# AFE.net
KiCad netlist of a schematic drawn in Altium Designer
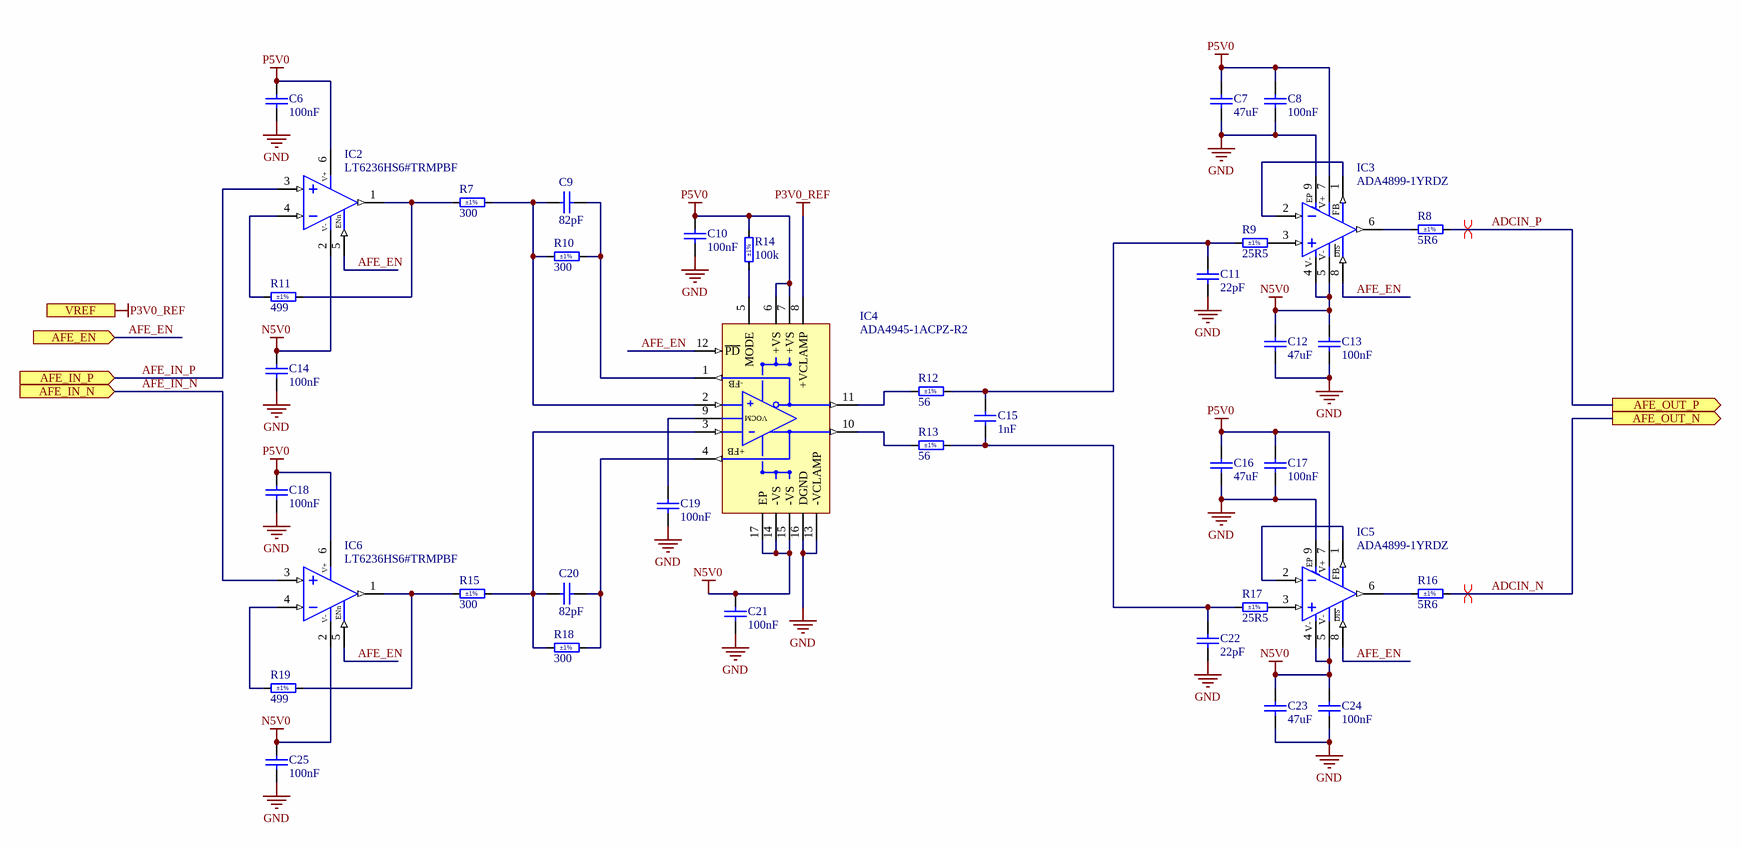
[diagram p0: AFE.SchDoc]

(export (version "E")
  (design (tool "Eeschema 10.0.6"))
  (components
    (comp (ref "C6")
      (value "100nF")
      (footprint "CAPC1005X55N")
      (description "Non-polarised capacitor")
      (fields
        (field (name "PART NUMBER") "CC0402_100NF_50V_10%_X7R")
        (field (name "VOLTAGE") "50V")
        (field (name "AUTHOR") "CERN DEM MR")
      )
      (libsource (lib "Capacitors") (part "Capacitor - non polarized"))
    )
    (comp (ref "C7")
      (value "47uF")
      (footprint "CAPC3216X180N")
      (description "Non-polarised capacitor")
      (fields
        (field (name "PART NUMBER") "CC1206_47UF_25V_20%_X5R")
        (field (name "VOLTAGE") "25V")
        (field (name "AUTHOR") "CERN DEM JLC")
      )
      (libsource (lib "Capacitors") (part "Capacitor - non polarized"))
    )
    (comp (ref "C8")
      (value "100nF")
      (footprint "CAPC1005X55N")
      (description "Non-polarised capacitor")
      (fields
        (field (name "PART NUMBER") "CC0402_100NF_50V_10%_X7R")
        (field (name "VOLTAGE") "50V")
        (field (name "AUTHOR") "CERN DEM MR")
      )
      (libsource (lib "Capacitors") (part "Capacitor - non polarized"))
    )
    (comp (ref "C9")
      (value "82pF")
      (footprint "CAPC1005X55N")
      (description "Non-polarised capacitor")
      (fields
        (field (name "PART NUMBER") "CC0402_82PF_25V_1%_C0G_KEMET_HiQ-CBR")
        (field (name "VOLTAGE") "25V")
        (field (name "AUTHOR") "CERN DEM MR")
      )
      (libsource (lib "Capacitors") (part "Capacitor - non polarized"))
    )
    (comp (ref "C10")
      (value "100nF")
      (footprint "CAPC1005X55N")
      (description "Non-polarised capacitor")
      (fields
        (field (name "PART NUMBER") "CC0402_100NF_50V_10%_X7R")
        (field (name "VOLTAGE") "50V")
        (field (name "AUTHOR") "CERN DEM MR")
      )
      (libsource (lib "Capacitors") (part "Capacitor - non polarized"))
    )
    (comp (ref "C11")
      (value "22pF")
      (footprint "CAPC1005X55N")
      (description "Non-polarised capacitor")
      (fields
        (field (name "PART NUMBER") "CC0402_22PF_50V_5%_C0G")
        (field (name "VOLTAGE") "50V")
        (field (name "AUTHOR") "CERN DEM JLC")
      )
      (libsource (lib "Capacitors") (part "Capacitor - non polarized"))
    )
    (comp (ref "C12")
      (value "47uF")
      (footprint "CAPC3216X180N")
      (description "Non-polarised capacitor")
      (fields
        (field (name "PART NUMBER") "CC1206_47UF_25V_20%_X5R")
        (field (name "VOLTAGE") "25V")
        (field (name "AUTHOR") "CERN DEM JLC")
      )
      (libsource (lib "Capacitors") (part "Capacitor - non polarized"))
    )
    (comp (ref "C13")
      (value "100nF")
      (footprint "CAPC1005X55N")
      (description "Non-polarised capacitor")
      (fields
        (field (name "PART NUMBER") "CC0402_100NF_50V_10%_X7R")
        (field (name "VOLTAGE") "50V")
        (field (name "AUTHOR") "CERN DEM MR")
      )
      (libsource (lib "Capacitors") (part "Capacitor - non polarized"))
    )
    (comp (ref "C14")
      (value "100nF")
      (footprint "CAPC1005X55N")
      (description "Non-polarised capacitor")
      (fields
        (field (name "PART NUMBER") "CC0402_100NF_50V_10%_X7R")
        (field (name "VOLTAGE") "50V")
        (field (name "AUTHOR") "CERN DEM MR")
      )
      (libsource (lib "Capacitors") (part "Capacitor - non polarized"))
    )
    (comp (ref "C15")
      (value "1nF")
      (footprint "CAPC1005X55N")
      (description "Non-polarised capacitor")
      (fields
        (field (name "PART NUMBER") "CC0402_1NF_50V_10%_X7R")
        (field (name "VOLTAGE") "50V")
        (field (name "AUTHOR") "CERN DEM JLC")
      )
      (libsource (lib "Capacitors") (part "Capacitor - non polarized"))
    )
    (comp (ref "C16")
      (value "47uF")
      (footprint "CAPC3216X180N")
      (description "Non-polarised capacitor")
      (fields
        (field (name "PART NUMBER") "CC1206_47UF_25V_20%_X5R")
        (field (name "VOLTAGE") "25V")
        (field (name "AUTHOR") "CERN DEM JLC")
      )
      (libsource (lib "Capacitors") (part "Capacitor - non polarized"))
    )
    (comp (ref "C17")
      (value "100nF")
      (footprint "CAPC1005X55N")
      (description "Non-polarised capacitor")
      (fields
        (field (name "PART NUMBER") "CC0402_100NF_50V_10%_X7R")
        (field (name "VOLTAGE") "50V")
        (field (name "AUTHOR") "CERN DEM MR")
      )
      (libsource (lib "Capacitors") (part "Capacitor - non polarized"))
    )
    (comp (ref "C18")
      (value "100nF")
      (footprint "CAPC1005X55N")
      (description "Non-polarised capacitor")
      (fields
        (field (name "PART NUMBER") "CC0402_100NF_50V_10%_X7R")
        (field (name "VOLTAGE") "50V")
        (field (name "AUTHOR") "CERN DEM MR")
      )
      (libsource (lib "Capacitors") (part "Capacitor - non polarized"))
    )
    (comp (ref "C19")
      (value "100nF")
      (footprint "CAPC1005X55N")
      (description "Non-polarised capacitor")
      (fields
        (field (name "PART NUMBER") "CC0402_100NF_50V_10%_X7R")
        (field (name "VOLTAGE") "50V")
        (field (name "AUTHOR") "CERN DEM MR")
      )
      (libsource (lib "Capacitors") (part "Capacitor - non polarized"))
    )
    (comp (ref "C20")
      (value "82pF")
      (footprint "CAPC1005X55N")
      (description "Non-polarised capacitor")
      (fields
        (field (name "PART NUMBER") "CC0402_82PF_25V_1%_C0G_KEMET_HiQ-CBR")
        (field (name "VOLTAGE") "25V")
        (field (name "AUTHOR") "CERN DEM MR")
      )
      (libsource (lib "Capacitors") (part "Capacitor - non polarized"))
    )
    (comp (ref "C21")
      (value "100nF")
      (footprint "CAPC1005X55N")
      (description "Non-polarised capacitor")
      (fields
        (field (name "PART NUMBER") "CC0402_100NF_50V_10%_X7R")
        (field (name "VOLTAGE") "50V")
        (field (name "AUTHOR") "CERN DEM MR")
      )
      (libsource (lib "Capacitors") (part "Capacitor - non polarized"))
    )
    (comp (ref "C22")
      (value "22pF")
      (footprint "CAPC1005X55N")
      (description "Non-polarised capacitor")
      (fields
        (field (name "PART NUMBER") "CC0402_22PF_50V_5%_C0G")
        (field (name "VOLTAGE") "50V")
        (field (name "AUTHOR") "CERN DEM JLC")
      )
      (libsource (lib "Capacitors") (part "Capacitor - non polarized"))
    )
    (comp (ref "C23")
      (value "47uF")
      (footprint "CAPC3216X180N")
      (description "Non-polarised capacitor")
      (fields
        (field (name "PART NUMBER") "CC1206_47UF_25V_20%_X5R")
        (field (name "VOLTAGE") "25V")
        (field (name "AUTHOR") "CERN DEM JLC")
      )
      (libsource (lib "Capacitors") (part "Capacitor - non polarized"))
    )
    (comp (ref "C24")
      (value "100nF")
      (footprint "CAPC1005X55N")
      (description "Non-polarised capacitor")
      (fields
        (field (name "PART NUMBER") "CC0402_100NF_50V_10%_X7R")
        (field (name "VOLTAGE") "50V")
        (field (name "AUTHOR") "CERN DEM MR")
      )
      (libsource (lib "Capacitors") (part "Capacitor - non polarized"))
    )
    (comp (ref "C25")
      (value "100nF")
      (footprint "CAPC1005X55N")
      (description "Non-polarised capacitor")
      (fields
        (field (name "PART NUMBER") "CC0402_100NF_50V_10%_X7R")
        (field (name "VOLTAGE") "50V")
        (field (name "AUTHOR") "CERN DEM MR")
      )
      (libsource (lib "Capacitors") (part "Capacitor - non polarized"))
    )
    (comp (ref "IC2")
      (value "LT6236HS6#TRMPBF")
      (footprint "SOT95P280X100-6N")
      (description "Rail-to-Rail Output 215MHz, 1.1nV/√Hz Op Amp/SAR ADC Driver")
      (fields (field (name "MANUFACTURER") "Linear Technology") (field (name "AUTHOR") "Michal Beldyga"))
      (libsource (lib "Semiconductors") (part "LT6236"))
    )
    (comp (ref "IC3")
      (value "ADA4899-1YRDZ")
      (footprint "SOIC127P600X175-9N-S229")
      (fields
        (field (name "MANUFACTURER") "ANALOG DEVICES")
        (field (name "MANUFACTURER PART NUMBER") "ADA4899-1YRD")
        (field (name "AUTHOR") "CERN DEM JLC")
      )
      (libsource (lib "ICs And Semiconductors") (part "ADA4899-1YRDZ"))
    )
    (comp (ref "IC4")
      (value "ADA4945-1ACPZ-R2")
      (footprint "QFN50P300X300X80_HS-17N")
      (description "High Speed, ±0.1 µV/˚C Offset Drift, Fully Differential ADC Driver")
      (fields (field (name "MANUFACTURER") "Analog Devices") (field (name "AUTHOR") "Michal Beldyga"))
      (libsource (lib "Semiconductors") (part "ADA4945-1"))
    )
    (comp (ref "IC5")
      (value "ADA4899-1YRDZ")
      (footprint "SOIC127P600X175-9N-S229")
      (fields
        (field (name "MANUFACTURER") "ANALOG DEVICES")
        (field (name "MANUFACTURER PART NUMBER") "ADA4899-1YRD")
        (field (name "AUTHOR") "CERN DEM JLC")
      )
      (libsource (lib "ICs And Semiconductors") (part "ADA4899-1YRDZ"))
    )
    (comp (ref "IC6")
      (value "LT6236HS6#TRMPBF")
      (footprint "SOT95P280X100-6N")
      (description "Rail-to-Rail Output 215MHz, 1.1nV/√Hz Op Amp/SAR ADC Driver")
      (fields (field (name "MANUFACTURER") "Linear Technology") (field (name "AUTHOR") "Michal Beldyga"))
      (libsource (lib "Semiconductors") (part "LT6236"))
    )
    (comp (ref "R7")
      (value "300")
      (footprint "RESC1005X40N")
      (description "Resistor - 1%")
      (fields
        (field (name "TOLERANCE") "±1%")
        (field (name "PART NUMBER") "R0402_300R_1%_0.0625W_100PPM")
        (field (name "POWER") "0.0625W")
        (field (name "AUTHOR") "CERN DEM JLC")
      )
      (libsource (lib "Resistors") (part "Resistor - 1%"))
    )
    (comp (ref "R8")
      (value "5R6")
      (footprint "RESC1608X55N")
      (description "Resistor - 1%")
      (fields
        (field (name "TOLERANCE") "±1%")
        (field (name "PART NUMBER") "R0603_5R6_1%_0.1W_200PPM")
        (field (name "POWER") "0.1W")
        (field (name "AUTHOR") "CERN DEM JLC")
      )
      (libsource (lib "Resistors") (part "Resistor - 1%"))
    )
    (comp (ref "R9")
      (value "25R5")
      (footprint "RESC1005X40N")
      (description "Resistor - 1%")
      (fields
        (field (name "TOLERANCE") "±1%")
        (field (name "PART NUMBER") "R0402_25R5_1%_0.0625W_100PPM")
        (field (name "POWER") "0.0625W")
        (field (name "AUTHOR") "CERN DEM JLC")
      )
      (libsource (lib "Resistors") (part "Resistor - 1%"))
    )
    (comp (ref "R10")
      (value "300")
      (footprint "RESC1005X40N")
      (description "Resistor - 1%")
      (fields
        (field (name "TOLERANCE") "±1%")
        (field (name "PART NUMBER") "R0402_300R_1%_0.0625W_100PPM")
        (field (name "POWER") "0.0625W")
        (field (name "AUTHOR") "CERN DEM JLC")
      )
      (libsource (lib "Resistors") (part "Resistor - 1%"))
    )
    (comp (ref "R11")
      (value "499")
      (footprint "RESC1005X40N")
      (description "Resistor - 1%")
      (fields
        (field (name "TOLERANCE") "±1%")
        (field (name "PART NUMBER") "R0402_499R_1%_0.1W_100PPM")
        (field (name "POWER") "0.1W")
        (field (name "AUTHOR") "CERN DEM MR")
      )
      (libsource (lib "Resistors") (part "Resistor - 1%"))
    )
    (comp (ref "R12")
      (value "56")
      (footprint "RESC1005X40N")
      (description "Resistor - 1%")
      (fields
        (field (name "TOLERANCE") "±1%")
        (field (name "PART NUMBER") "R0402_56R_1%_0.0625W_100PPM")
        (field (name "POWER") "0.0625W")
        (field (name "AUTHOR") "CERN DEM JLC")
      )
      (libsource (lib "Resistors") (part "Resistor - 1%"))
    )
    (comp (ref "R13")
      (value "56")
      (footprint "RESC1005X40N")
      (description "Resistor - 1%")
      (fields
        (field (name "TOLERANCE") "±1%")
        (field (name "PART NUMBER") "R0402_56R_1%_0.0625W_100PPM")
        (field (name "POWER") "0.0625W")
        (field (name "AUTHOR") "CERN DEM JLC")
      )
      (libsource (lib "Resistors") (part "Resistor - 1%"))
    )
    (comp (ref "R14")
      (value "100k")
      (footprint "RESC1005X40N")
      (description "Resistor - 1%")
      (fields
        (field (name "TOLERANCE") "±1%")
        (field (name "PART NUMBER") "R0402_100K_1%_0.0625W_100PPM")
        (field (name "POWER") "0.0625W")
        (field (name "AUTHOR") "CERN DEM JLC")
      )
      (libsource (lib "Resistors") (part "Resistor - 1%"))
    )
    (comp (ref "R15")
      (value "300")
      (footprint "RESC1005X40N")
      (description "Resistor - 1%")
      (fields
        (field (name "TOLERANCE") "±1%")
        (field (name "PART NUMBER") "R0402_300R_1%_0.0625W_100PPM")
        (field (name "POWER") "0.0625W")
        (field (name "AUTHOR") "CERN DEM JLC")
      )
      (libsource (lib "Resistors") (part "Resistor - 1%"))
    )
    (comp (ref "R16")
      (value "5R6")
      (footprint "RESC1608X55N")
      (description "Resistor - 1%")
      (fields
        (field (name "TOLERANCE") "±1%")
        (field (name "PART NUMBER") "R0603_5R6_1%_0.1W_200PPM")
        (field (name "POWER") "0.1W")
        (field (name "AUTHOR") "CERN DEM JLC")
      )
      (libsource (lib "Resistors") (part "Resistor - 1%"))
    )
    (comp (ref "R17")
      (value "25R5")
      (footprint "RESC1005X40N")
      (description "Resistor - 1%")
      (fields
        (field (name "TOLERANCE") "±1%")
        (field (name "PART NUMBER") "R0402_25R5_1%_0.0625W_100PPM")
        (field (name "POWER") "0.0625W")
        (field (name "AUTHOR") "CERN DEM JLC")
      )
      (libsource (lib "Resistors") (part "Resistor - 1%"))
    )
    (comp (ref "R18")
      (value "300")
      (footprint "RESC1005X40N")
      (description "Resistor - 1%")
      (fields
        (field (name "TOLERANCE") "±1%")
        (field (name "PART NUMBER") "R0402_300R_1%_0.0625W_100PPM")
        (field (name "POWER") "0.0625W")
        (field (name "AUTHOR") "CERN DEM JLC")
      )
      (libsource (lib "Resistors") (part "Resistor - 1%"))
    )
    (comp (ref "R19")
      (value "499")
      (footprint "RESC1005X40N")
      (description "Resistor - 1%")
      (fields
        (field (name "TOLERANCE") "±1%")
        (field (name "PART NUMBER") "R0402_499R_1%_0.1W_100PPM")
        (field (name "POWER") "0.1W")
        (field (name "AUTHOR") "CERN DEM MR")
      )
      (libsource (lib "Resistors") (part "Resistor - 1%"))
    )
  )
  (nets
    (net (code "1") (name "/ADCIN_N") (class "Default")
      (node (ref "R16") (pin "2") (pinfunction "2_2") (pintype "passive"))
    )
    (net (code "2") (name "/ADCIN_P") (class "Default")
      (node (ref "R8") (pin "2") (pinfunction "2_2") (pintype "passive"))
    )
    (net (code "3") (name "/AFE_EN") (class "Default")
      (node (ref "IC2") (pin "5") (pinfunction "~{DIS}_5") (pintype "input"))
      (node (ref "IC3") (pin "8") (pinfunction "~{DIS}_8") (pintype "input"))
      (node (ref "IC4") (pin "12") (pinfunction "~{PD}_12") (pintype "input"))
      (node (ref "IC5") (pin "8") (pinfunction "~{DIS}_8") (pintype "input"))
      (node (ref "IC6") (pin "5") (pinfunction "~{DIS}_5") (pintype "input"))
    )
    (net (code "4") (name "/AFE_IN_N") (class "Default")
      (node (ref "IC6") (pin "3") (pinfunction "VP_3") (pintype "input"))
    )
    (net (code "5") (name "/AFE_IN_P") (class "Default")
      (node (ref "IC2") (pin "3") (pinfunction "VP_3") (pintype "input"))
    )
    (net (code "6") (name "GND") (class "Default")
      (node (ref "C10") (pin "1") (pinfunction "1_1") (pintype "passive"))
      (node (ref "C11") (pin "1") (pinfunction "1_1") (pintype "passive"))
      (node (ref "C12") (pin "1") (pinfunction "1_1") (pintype "passive"))
      (node (ref "C13") (pin "1") (pinfunction "1_1") (pintype "passive"))
      (node (ref "C14") (pin "1") (pinfunction "1_1") (pintype "passive"))
      (node (ref "C16") (pin "1") (pinfunction "1_1") (pintype "passive"))
      (node (ref "C17") (pin "1") (pinfunction "1_1") (pintype "passive"))
      (node (ref "C18") (pin "1") (pinfunction "1_1") (pintype "passive"))
      (node (ref "C19") (pin "1") (pinfunction "1_1") (pintype "passive"))
      (node (ref "C21") (pin "1") (pinfunction "1_1") (pintype "passive"))
      (node (ref "C22") (pin "1") (pinfunction "1_1") (pintype "passive"))
      (node (ref "C23") (pin "1") (pinfunction "1_1") (pintype "passive"))
      (node (ref "C24") (pin "1") (pinfunction "1_1") (pintype "passive"))
      (node (ref "C25") (pin "1") (pinfunction "1_1") (pintype "passive"))
      (node (ref "C6") (pin "1") (pinfunction "1_1") (pintype "passive"))
      (node (ref "C7") (pin "1") (pinfunction "1_1") (pintype "passive"))
      (node (ref "C8") (pin "1") (pinfunction "1_1") (pintype "passive"))
      (node (ref "IC3") (pin "9") (pinfunction "EP_9") (pintype "power_in"))
      (node (ref "IC4") (pin "13") (pinfunction "-VCLAMP_13") (pintype "power_in"))
      (node (ref "IC4") (pin "16") (pinfunction "DGND_16") (pintype "power_in"))
      (node (ref "IC5") (pin "9") (pinfunction "EP_9") (pintype "power_in"))
    )
    (net (code "7") (name "N5V0") (class "Default")
      (node (ref "C12") (pin "2") (pinfunction "2_2") (pintype "passive"))
      (node (ref "C13") (pin "2") (pinfunction "2_2") (pintype "passive"))
      (node (ref "C14") (pin "2") (pinfunction "2_2") (pintype "passive"))
      (node (ref "C21") (pin "2") (pinfunction "2_2") (pintype "passive"))
      (node (ref "C23") (pin "2") (pinfunction "2_2") (pintype "passive"))
      (node (ref "C24") (pin "2") (pinfunction "2_2") (pintype "passive"))
      (node (ref "C25") (pin "2") (pinfunction "2_2") (pintype "passive"))
      (node (ref "IC2") (pin "2") (pinfunction "GND_2") (pintype "power_in"))
      (node (ref "IC3") (pin "4") (pinfunction "V-_4") (pintype "power_in"))
      (node (ref "IC3") (pin "5") (pinfunction "V-_5") (pintype "power_in"))
      (node (ref "IC4") (pin "14") (pinfunction "-VS_14") (pintype "power_in"))
      (node (ref "IC4") (pin "15") (pinfunction "-VS_15") (pintype "power_in"))
      (node (ref "IC4") (pin "17") (pinfunction "EP_17") (pintype "power_in"))
      (node (ref "IC5") (pin "4") (pinfunction "V-_4") (pintype "power_in"))
      (node (ref "IC5") (pin "5") (pinfunction "V-_5") (pintype "power_in"))
      (node (ref "IC6") (pin "2") (pinfunction "GND_2") (pintype "power_in"))
    )
    (net (code "8") (name "Net-(C11-Pad2)") (class "Default")
      (node (ref "C11") (pin "2") (pinfunction "2_2") (pintype "passive"))
      (node (ref "C15") (pin "2") (pinfunction "2_2") (pintype "passive"))
      (node (ref "R12") (pin "2") (pinfunction "2_2") (pintype "passive"))
      (node (ref "R9") (pin "1") (pinfunction "1_1") (pintype "passive"))
    )
    (net (code "9") (name "Net-(C15-Pad1)") (class "Default")
      (node (ref "C15") (pin "1") (pinfunction "1_1") (pintype "passive"))
      (node (ref "C22") (pin "2") (pinfunction "2_2") (pintype "passive"))
      (node (ref "R13") (pin "2") (pinfunction "2_2") (pintype "passive"))
      (node (ref "R17") (pin "1") (pinfunction "1_1") (pintype "passive"))
    )
    (net (code "10") (name "Net-(IC2-VN)") (class "Default")
      (node (ref "IC2") (pin "4") (pinfunction "VN_4") (pintype "input"))
      (node (ref "R11") (pin "1") (pinfunction "1_1") (pintype "passive"))
    )
    (net (code "11") (name "Net-(IC2-q)") (class "Default")
      (node (ref "IC2") (pin "1") (pinfunction "q_1") (pintype "output"))
      (node (ref "R11") (pin "2") (pinfunction "2_2") (pintype "passive"))
      (node (ref "R7") (pin "1") (pinfunction "1_1") (pintype "passive"))
    )
    (net (code "12") (name "Net-(IC3-FB)") (class "Default")
      (node (ref "IC3") (pin "1") (pinfunction "FB_1") (pintype "output"))
      (node (ref "IC3") (pin "2") (pinfunction "IN-_2") (pintype "input"))
    )
    (net (code "13") (name "Net-(IC3-IN+)") (class "Default")
      (node (ref "IC3") (pin "3") (pinfunction "IN+_3") (pintype "input"))
      (node (ref "R9") (pin "2") (pinfunction "2_2") (pintype "passive"))
    )
    (net (code "14") (name "Net-(IC3-OUT)") (class "Default")
      (node (ref "IC3") (pin "6") (pinfunction "OUT_6") (pintype "output"))
      (node (ref "R8") (pin "1") (pinfunction "1_1") (pintype "passive"))
    )
    (net (code "15") (name "Net-(IC4-+FB)") (class "Default")
      (node (ref "C20") (pin "2") (pinfunction "2_2") (pintype "passive"))
      (node (ref "IC4") (pin "4") (pinfunction "+FB_4") (pintype "output"))
      (node (ref "R18") (pin "2") (pinfunction "2_2") (pintype "passive"))
    )
    (net (code "16") (name "Net-(IC4-+IN)") (class "Default")
      (node (ref "C9") (pin "1") (pinfunction "1_1") (pintype "passive"))
      (node (ref "IC4") (pin "2") (pinfunction "+IN_2") (pintype "input"))
      (node (ref "R10") (pin "1") (pinfunction "1_1") (pintype "passive"))
      (node (ref "R7") (pin "2") (pinfunction "2_2") (pintype "passive"))
    )
    (net (code "17") (name "Net-(IC4-+OUT)") (class "Default")
      (node (ref "IC4") (pin "10") (pinfunction "+OUT_10") (pintype "output"))
      (node (ref "R13") (pin "1") (pinfunction "1_1") (pintype "passive"))
    )
    (net (code "18") (name "Net-(IC4--FB)") (class "Default")
      (node (ref "C9") (pin "2") (pinfunction "2_2") (pintype "passive"))
      (node (ref "IC4") (pin "1") (pinfunction "-FB_1") (pintype "output"))
      (node (ref "R10") (pin "2") (pinfunction "2_2") (pintype "passive"))
    )
    (net (code "19") (name "Net-(IC4--IN)") (class "Default")
      (node (ref "C20") (pin "1") (pinfunction "1_1") (pintype "passive"))
      (node (ref "IC4") (pin "3") (pinfunction "-IN_3") (pintype "input"))
      (node (ref "R15") (pin "2") (pinfunction "2_2") (pintype "passive"))
      (node (ref "R18") (pin "1") (pinfunction "1_1") (pintype "passive"))
    )
    (net (code "20") (name "Net-(IC4--OUT)") (class "Default")
      (node (ref "IC4") (pin "11") (pinfunction "-OUT_11") (pintype "output"))
      (node (ref "R12") (pin "1") (pinfunction "1_1") (pintype "passive"))
    )
    (net (code "21") (name "Net-(IC4-MODE)") (class "Default")
      (node (ref "IC4") (pin "5") (pinfunction "MODE_5") (pintype "power_in"))
      (node (ref "R14") (pin "1") (pinfunction "1_1") (pintype "passive"))
    )
    (net (code "22") (name "Net-(IC4-VOCM)") (class "Default")
      (node (ref "C19") (pin "2") (pinfunction "2_2") (pintype "passive"))
      (node (ref "IC4") (pin "9") (pinfunction "VOCM_9") (pintype "passive"))
    )
    (net (code "23") (name "Net-(IC5-FB)") (class "Default")
      (node (ref "IC5") (pin "1") (pinfunction "FB_1") (pintype "output"))
      (node (ref "IC5") (pin "2") (pinfunction "IN-_2") (pintype "input"))
    )
    (net (code "24") (name "Net-(IC5-IN+)") (class "Default")
      (node (ref "IC5") (pin "3") (pinfunction "IN+_3") (pintype "input"))
      (node (ref "R17") (pin "2") (pinfunction "2_2") (pintype "passive"))
    )
    (net (code "25") (name "Net-(IC5-OUT)") (class "Default")
      (node (ref "IC5") (pin "6") (pinfunction "OUT_6") (pintype "output"))
      (node (ref "R16") (pin "1") (pinfunction "1_1") (pintype "passive"))
    )
    (net (code "26") (name "Net-(IC6-VN)") (class "Default")
      (node (ref "IC6") (pin "4") (pinfunction "VN_4") (pintype "input"))
      (node (ref "R19") (pin "1") (pinfunction "1_1") (pintype "passive"))
    )
    (net (code "27") (name "Net-(IC6-q)") (class "Default")
      (node (ref "IC6") (pin "1") (pinfunction "q_1") (pintype "output"))
      (node (ref "R15") (pin "1") (pinfunction "1_1") (pintype "passive"))
      (node (ref "R19") (pin "2") (pinfunction "2_2") (pintype "passive"))
    )
    (net (code "28") (name "P3V0_REF") (class "Default")
      (node (ref "IC4") (pin "8") (pinfunction "+VCLAMP_8") (pintype "power_in"))
    )
    (net (code "29") (name "P5V0") (class "Default")
      (node (ref "C10") (pin "2") (pinfunction "2_2") (pintype "passive"))
      (node (ref "C16") (pin "2") (pinfunction "2_2") (pintype "passive"))
      (node (ref "C17") (pin "2") (pinfunction "2_2") (pintype "passive"))
      (node (ref "C18") (pin "2") (pinfunction "2_2") (pintype "passive"))
      (node (ref "C6") (pin "2") (pinfunction "2_2") (pintype "passive"))
      (node (ref "C7") (pin "2") (pinfunction "2_2") (pintype "passive"))
      (node (ref "C8") (pin "2") (pinfunction "2_2") (pintype "passive"))
      (node (ref "IC2") (pin "6") (pinfunction "VCC_6") (pintype "power_in"))
      (node (ref "IC3") (pin "7") (pinfunction "V+_7") (pintype "power_in"))
      (node (ref "IC4") (pin "6") (pinfunction "+VS_6") (pintype "power_in"))
      (node (ref "IC4") (pin "7") (pinfunction "+VS_7") (pintype "power_in"))
      (node (ref "IC5") (pin "7") (pinfunction "V+_7") (pintype "power_in"))
      (node (ref "IC6") (pin "6") (pinfunction "VCC_6") (pintype "power_in"))
      (node (ref "R14") (pin "2") (pinfunction "2_2") (pintype "passive"))
    )
  )
)
